# 3_-28pins_sch.net
KiCad netlist of a schematic drawn in Altium Designer
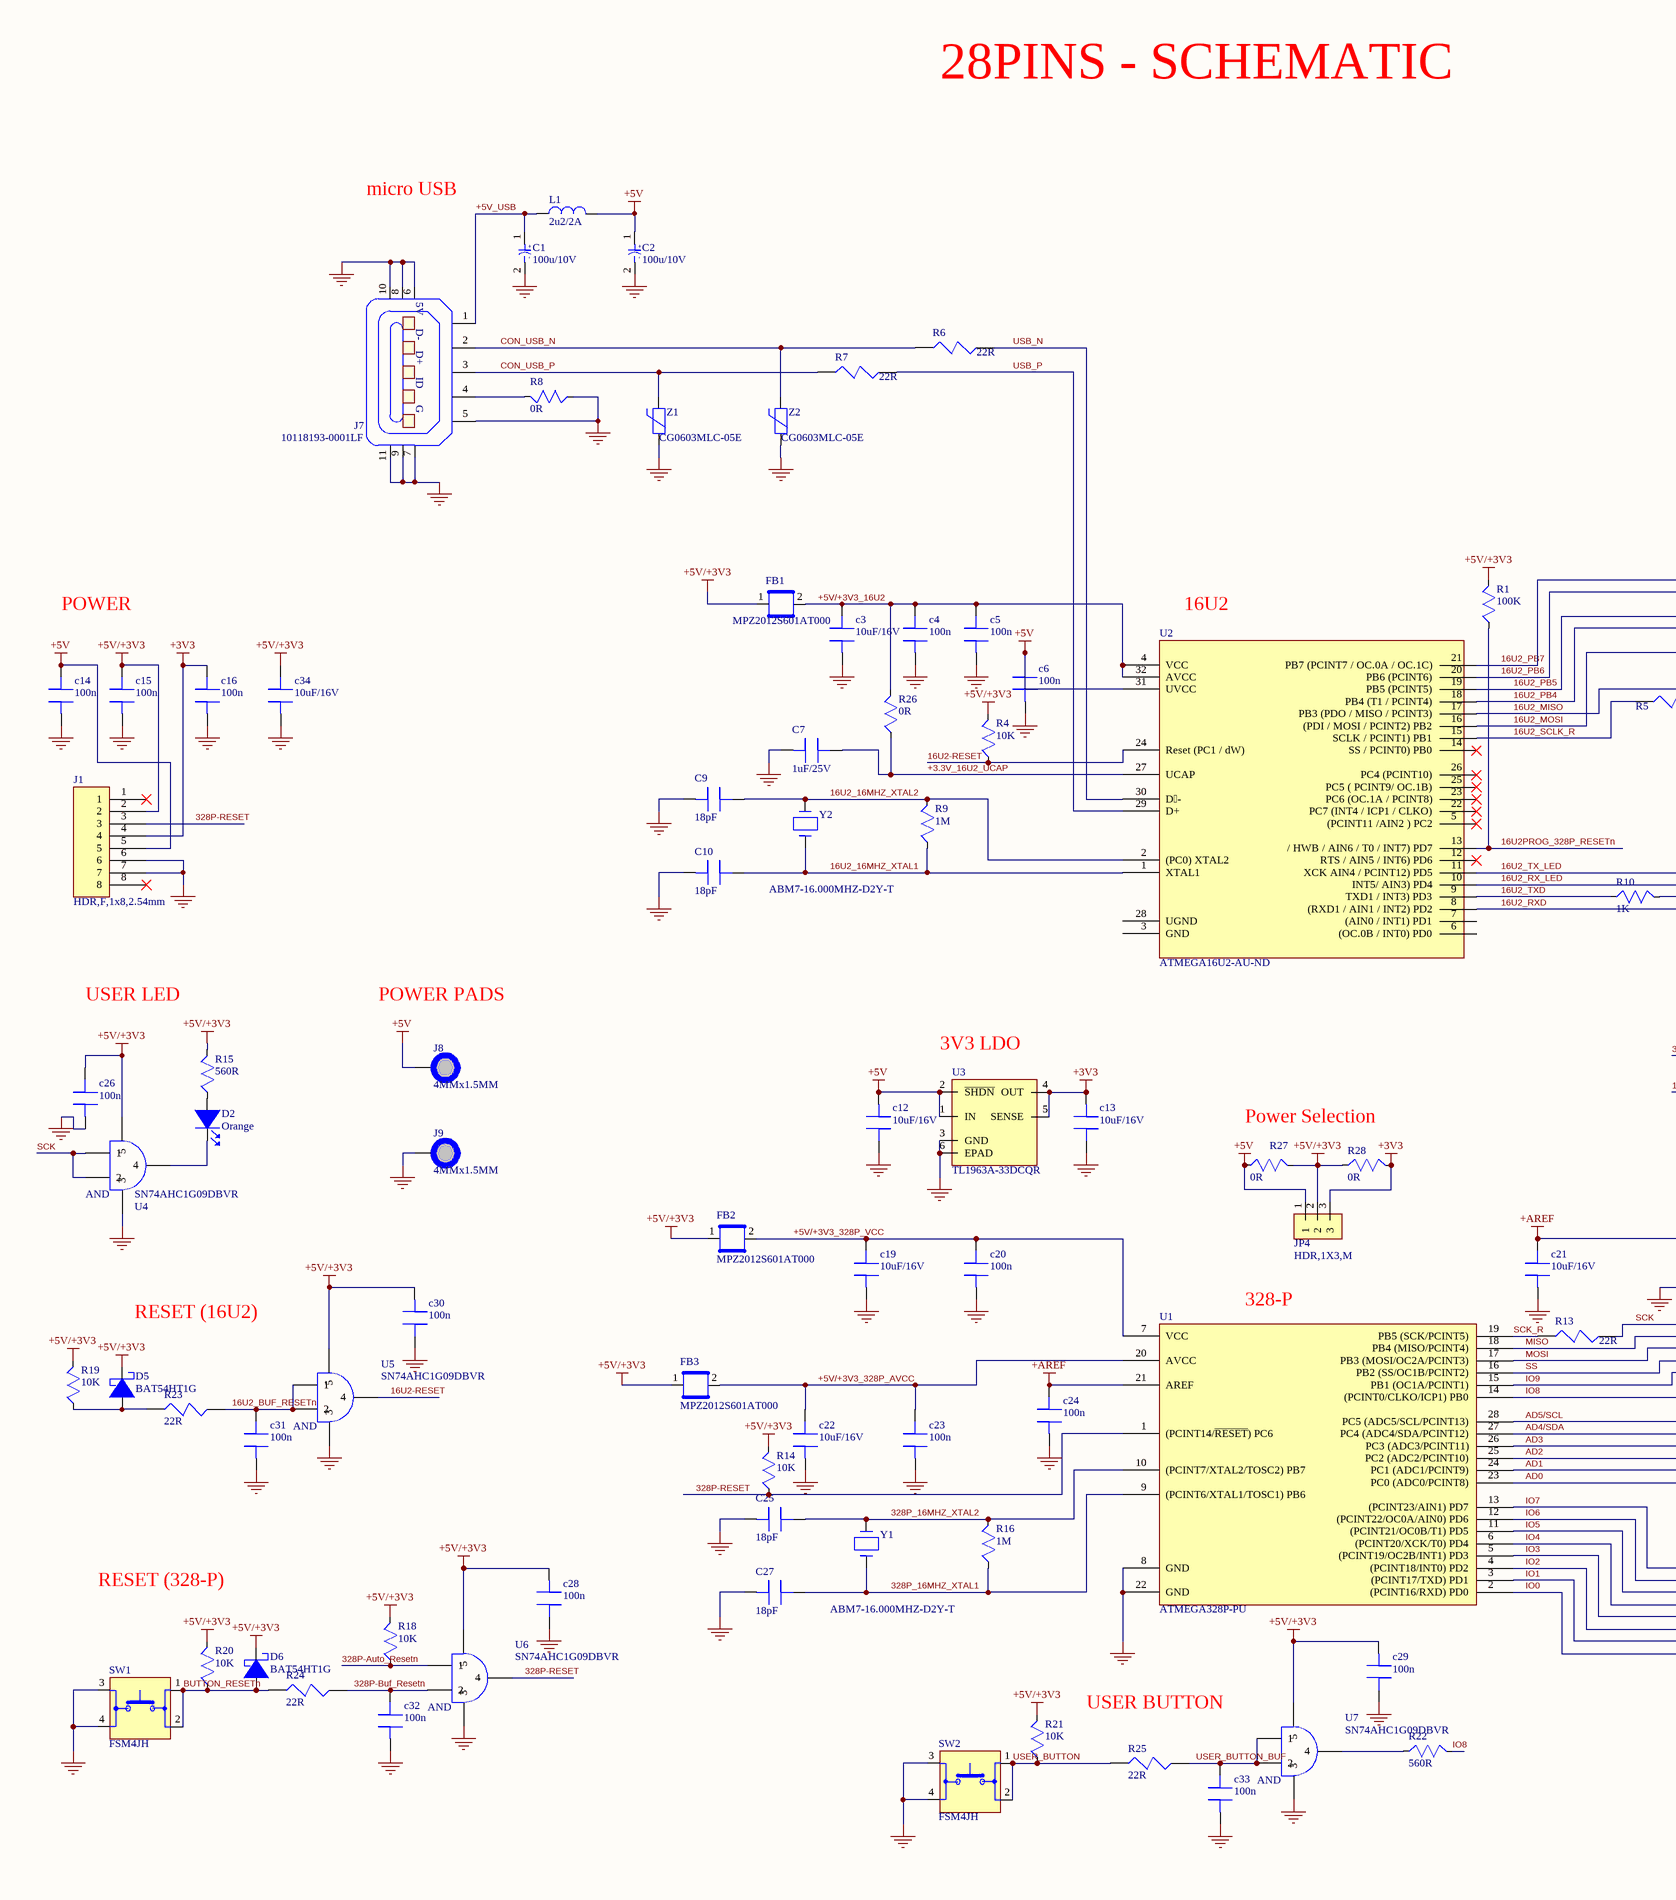
[diagram p0: [3] -28pins_sch.SchDoc, left]
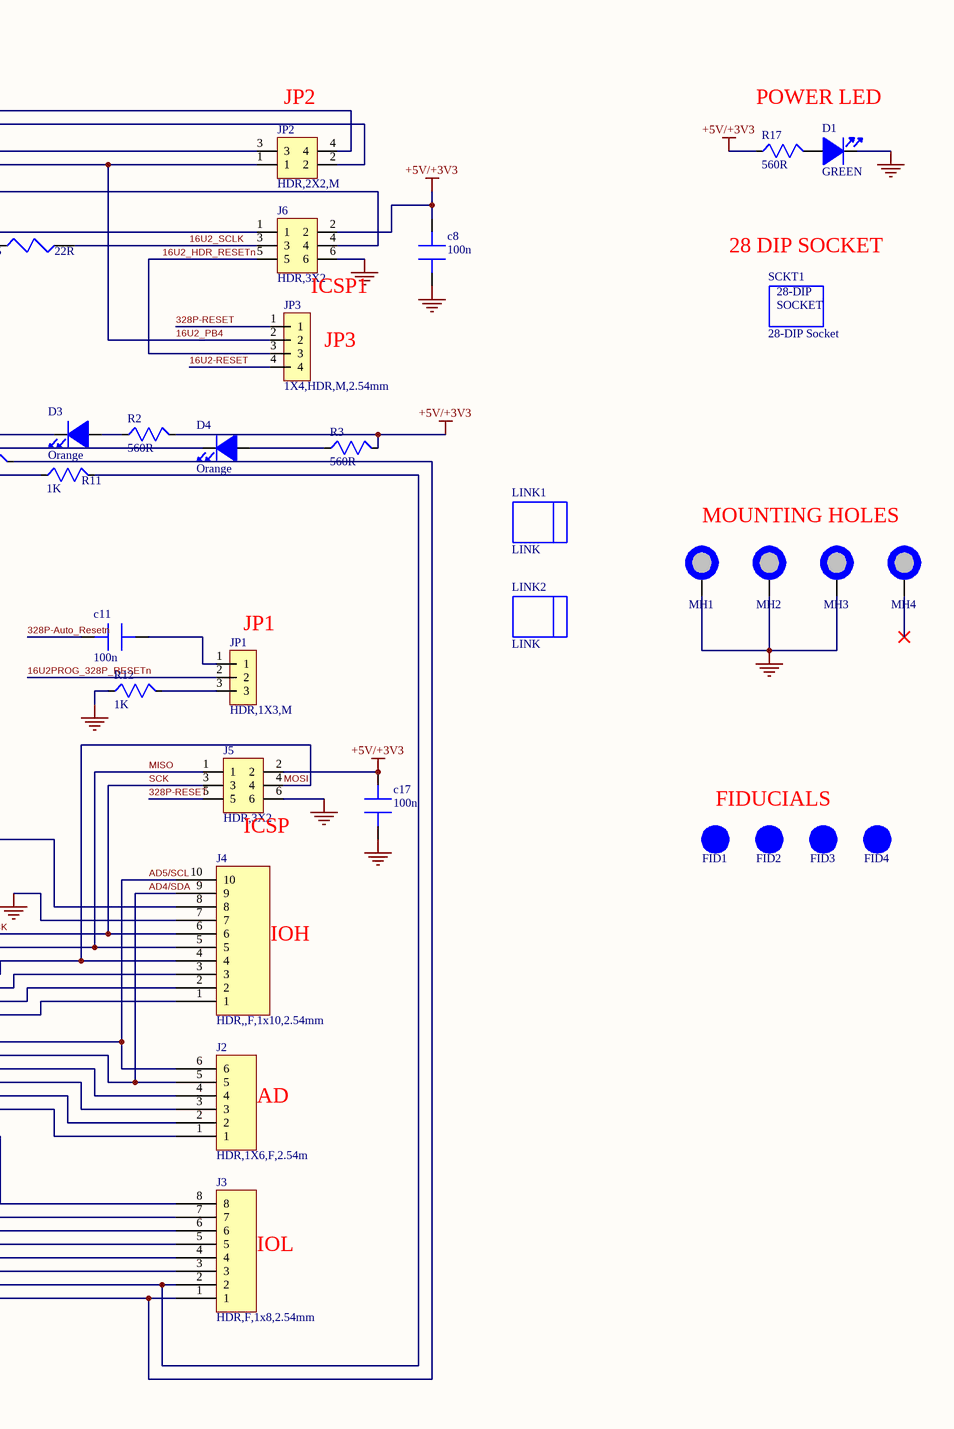
[diagram p1: [3] -28pins_sch.SchDoc, right]

(export (version "E")
  (design (tool "Eeschema 10.0.6"))
  (components
    (comp (ref "C1")
      (value "100u/10V")
      (footprint "C_ALUM")
      (fields
        (field (name "MANUFACTURER") "Panasonic")
        (field (name "MANUFACTURER PART NUMBER") "EEE-1AA101WR")
      )
      (libsource (lib "28pins_Schlib1") (part "EEE-1AA101WR"))
    )
    (comp (ref "C2")
      (value "100u/10V")
      (footprint "C_ALUM")
      (fields
        (field (name "MANUFACTURER") "Panasonic")
        (field (name "MANUFACTURER PART NUMBER") "EEE-1AA101WR")
      )
      (libsource (lib "28pins_Schlib1") (part "EEE-1AA101WR"))
    )
    (comp (ref "c3")
      (value "10uF/16V")
      (footprint "X5R 0805")
      (fields
        (field (name "MANUFACTURER") "TDK")
        (field (name "MANUFACTURER PART NUMBER") "C2012X5R1C106K085AC")
      )
      (libsource (lib "28pins_Schlib1") (part "C2012X5R1C106K085AC"))
    )
    (comp (ref "c4")
      (value "100n")
      (footprint "C0805")
      (fields
        (field (name "MANUFACTURER") "Samsung")
        (field (name "MANUFACTURER PART NUMBER") "CL21B104KBCNNNC")
      )
      (libsource (lib "28pins_Schlib1") (part "CL21B104KBCNNNC"))
    )
    (comp (ref "c5")
      (value "100n")
      (footprint "C0805")
      (fields
        (field (name "MANUFACTURER") "Samsung")
        (field (name "MANUFACTURER PART NUMBER") "CL21B104KBCNNNC")
      )
      (libsource (lib "28pins_Schlib1") (part "CL21B104KBCNNNC"))
    )
    (comp (ref "c6")
      (value "100n")
      (footprint "C0805")
      (fields
        (field (name "MANUFACTURER") "Samsung")
        (field (name "MANUFACTURER PART NUMBER") "CL21B104KBCNNNC")
      )
      (libsource (lib "28pins_Schlib1") (part "CL21B104KBCNNNC"))
    )
    (comp (ref "C7")
      (value "1uF/25V")
      (footprint "C0805")
      (fields
        (field (name "MANUFACTURER") "TDK")
        (field (name "MANUFACTURER PART NUMBER") "C2012X5R1E105K125AA")
      )
      (libsource (lib "28pins_Schlib1") (part "C2012X5R1E105K125AA"))
    )
    (comp (ref "c8")
      (value "100n")
      (footprint "C0805")
      (fields
        (field (name "MANUFACTURER") "Samsung")
        (field (name "MANUFACTURER PART NUMBER") "CL21B104KBCNNNC")
      )
      (libsource (lib "28pins_Schlib1") (part "CL21B104KBCNNNC"))
    )
    (comp (ref "C9")
      (value "18pF")
      (footprint "C0805")
      (fields
        (field (name "MANUFACTURER") "KEMET")
        (field (name "MANUFACTURER PART NUMBER") "C0805C180K5RACTU")
      )
      (libsource (lib "28pins_Schlib1") (part "C0805C180K5RACTU"))
    )
    (comp (ref "C10")
      (value "18pF")
      (footprint "C0805")
      (fields
        (field (name "MANUFACTURER") "KEMET")
        (field (name "MANUFACTURER PART NUMBER") "C0805C180K5RACTU")
      )
      (libsource (lib "28pins_Schlib1") (part "C0805C180K5RACTU"))
    )
    (comp (ref "c11")
      (value "100n")
      (footprint "C0805")
      (fields
        (field (name "MANUFACTURER") "Samsung")
        (field (name "MANUFACTURER PART NUMBER") "CL21B104KBCNNNC")
      )
      (libsource (lib "28pins_Schlib1") (part "CL21B104KBCNNNC"))
    )
    (comp (ref "c12")
      (value "10uF/16V")
      (footprint "X5R 0805")
      (fields
        (field (name "MANUFACTURER") "TDK")
        (field (name "MANUFACTURER PART NUMBER") "C2012X5R1C106K085AC")
      )
      (libsource (lib "28pins_Schlib1") (part "C2012X5R1C106K085AC"))
    )
    (comp (ref "c13")
      (value "10uF/16V")
      (footprint "X5R 0805")
      (fields
        (field (name "MANUFACTURER") "TDK")
        (field (name "MANUFACTURER PART NUMBER") "C2012X5R1C106K085AC")
      )
      (libsource (lib "28pins_Schlib1") (part "C2012X5R1C106K085AC"))
    )
    (comp (ref "c14")
      (value "100n")
      (footprint "C0805")
      (fields
        (field (name "MANUFACTURER") "Samsung")
        (field (name "MANUFACTURER PART NUMBER") "CL21B104KBCNNNC")
      )
      (libsource (lib "28pins_Schlib1") (part "CL21B104KBCNNNC"))
    )
    (comp (ref "c15")
      (value "100n")
      (footprint "C0805")
      (fields
        (field (name "MANUFACTURER") "Samsung")
        (field (name "MANUFACTURER PART NUMBER") "CL21B104KBCNNNC")
      )
      (libsource (lib "28pins_Schlib1") (part "CL21B104KBCNNNC"))
    )
    (comp (ref "c16")
      (value "100n")
      (footprint "C0805")
      (fields
        (field (name "MANUFACTURER") "Samsung")
        (field (name "MANUFACTURER PART NUMBER") "CL21B104KBCNNNC")
      )
      (libsource (lib "28pins_Schlib1") (part "CL21B104KBCNNNC"))
    )
    (comp (ref "c17")
      (value "100n")
      (footprint "C0805")
      (fields
        (field (name "MANUFACTURER") "Samsung")
        (field (name "MANUFACTURER PART NUMBER") "CL21B104KBCNNNC")
      )
      (libsource (lib "28pins_Schlib1") (part "CL21B104KBCNNNC"))
    )
    (comp (ref "c19")
      (value "10uF/16V")
      (footprint "X5R 0805")
      (fields
        (field (name "MANUFACTURER") "TDK")
        (field (name "MANUFACTURER PART NUMBER") "C2012X5R1C106K085AC")
      )
      (libsource (lib "28pins_Schlib1") (part "C2012X5R1C106K085AC"))
    )
    (comp (ref "c20")
      (value "100n")
      (footprint "C0805")
      (fields
        (field (name "MANUFACTURER") "Samsung")
        (field (name "MANUFACTURER PART NUMBER") "CL21B104KBCNNNC")
      )
      (libsource (lib "28pins_Schlib1") (part "CL21B104KBCNNNC"))
    )
    (comp (ref "c21")
      (value "10uF/16V")
      (footprint "X5R 0805")
      (fields
        (field (name "MANUFACTURER") "TDK")
        (field (name "MANUFACTURER PART NUMBER") "C2012X5R1C106K085AC")
      )
      (libsource (lib "28pins_Schlib1") (part "C2012X5R1C106K085AC"))
    )
    (comp (ref "c22")
      (value "10uF/16V")
      (footprint "X5R 0805")
      (fields
        (field (name "MANUFACTURER") "TDK")
        (field (name "MANUFACTURER PART NUMBER") "C2012X5R1C106K085AC")
      )
      (libsource (lib "28pins_Schlib1") (part "C2012X5R1C106K085AC"))
    )
    (comp (ref "c23")
      (value "100n")
      (footprint "C0805")
      (fields
        (field (name "MANUFACTURER") "Samsung")
        (field (name "MANUFACTURER PART NUMBER") "CL21B104KBCNNNC")
      )
      (libsource (lib "28pins_Schlib1") (part "CL21B104KBCNNNC"))
    )
    (comp (ref "c24")
      (value "100n")
      (footprint "C0805")
      (fields
        (field (name "MANUFACTURER") "Samsung")
        (field (name "MANUFACTURER PART NUMBER") "CL21B104KBCNNNC")
      )
      (libsource (lib "28pins_Schlib1") (part "CL21B104KBCNNNC"))
    )
    (comp (ref "C25")
      (value "18pF")
      (footprint "C0805")
      (fields
        (field (name "MANUFACTURER") "KEMET")
        (field (name "MANUFACTURER PART NUMBER") "C0805C180K5RACTU")
      )
      (libsource (lib "28pins_Schlib1") (part "C0805C180K5RACTU"))
    )
    (comp (ref "c26")
      (value "100n")
      (footprint "C0805")
      (fields
        (field (name "MANUFACTURER") "Samsung")
        (field (name "MANUFACTURER PART NUMBER") "CL21B104KBCNNNC")
      )
      (libsource (lib "28pins_Schlib1") (part "CL21B104KBCNNNC"))
    )
    (comp (ref "C27")
      (value "18pF")
      (footprint "C0805")
      (fields
        (field (name "MANUFACTURER") "KEMET")
        (field (name "MANUFACTURER PART NUMBER") "C0805C180K5RACTU")
      )
      (libsource (lib "28pins_Schlib1") (part "C0805C180K5RACTU"))
    )
    (comp (ref "c28")
      (value "100n")
      (footprint "C0805")
      (fields
        (field (name "MANUFACTURER") "Samsung")
        (field (name "MANUFACTURER PART NUMBER") "CL21B104KBCNNNC")
      )
      (libsource (lib "28pins_Schlib1") (part "CL21B104KBCNNNC"))
    )
    (comp (ref "c29")
      (value "100n")
      (footprint "C0805")
      (fields
        (field (name "MANUFACTURER") "Samsung")
        (field (name "MANUFACTURER PART NUMBER") "CL21B104KBCNNNC")
      )
      (libsource (lib "28pins_Schlib1") (part "CL21B104KBCNNNC"))
    )
    (comp (ref "c30")
      (value "100n")
      (footprint "C0805")
      (fields
        (field (name "MANUFACTURER") "Samsung")
        (field (name "MANUFACTURER PART NUMBER") "CL21B104KBCNNNC")
      )
      (libsource (lib "28pins_Schlib1") (part "CL21B104KBCNNNC"))
    )
    (comp (ref "c31")
      (value "100n")
      (footprint "C0805")
      (fields
        (field (name "MANUFACTURER") "Samsung")
        (field (name "MANUFACTURER PART NUMBER") "CL21B104KBCNNNC")
      )
      (libsource (lib "28pins_Schlib1") (part "CL21B104KBCNNNC"))
    )
    (comp (ref "c32")
      (value "100n")
      (footprint "C0805")
      (fields
        (field (name "MANUFACTURER") "Samsung")
        (field (name "MANUFACTURER PART NUMBER") "CL21B104KBCNNNC")
      )
      (libsource (lib "28pins_Schlib1") (part "CL21B104KBCNNNC"))
    )
    (comp (ref "c33")
      (value "100n")
      (footprint "C0805")
      (fields
        (field (name "MANUFACTURER") "Samsung")
        (field (name "MANUFACTURER PART NUMBER") "CL21B104KBCNNNC")
      )
      (libsource (lib "28pins_Schlib1") (part "CL21B104KBCNNNC"))
    )
    (comp (ref "c34")
      (value "10uF/16V")
      (footprint "X5R 0805")
      (fields
        (field (name "MANUFACTURER") "TDK")
        (field (name "MANUFACTURER PART NUMBER") "C2012X5R1C106K085AC")
      )
      (libsource (lib "28pins_Schlib1") (part "C2012X5R1C106K085AC"))
    )
    (comp (ref "D1")
      (value "GREEN")
      (footprint "LED_0603")
      (description "Single Color LED")
      (fields
        (field (name "MANUFACTURER") "SunLED")
        (field (name "MANUFACTURER PART NUMBER") "XZCDGK53W-8VF")
      )
      (libsource (lib "28pins_Schlib1") (part "XZCDGK53W-8VF"))
    )
    (comp (ref "D2")
      (value "Orange")
      (footprint "LED_0603")
      (description "Single Color LED Array, Orange, Transparent Clear, 1.2mm")
      (fields (field (name "MANUFACTURER") "Rohm") (field (name "MANUFACTURER PART NUMBER") "SML-311DTT86"))
      (libsource (lib "28pins_Schlib1") (part "SML-311DTT86"))
    )
    (comp (ref "D3")
      (value "Orange")
      (footprint "LED_0603")
      (description "Single Color LED Array, Orange, Transparent Clear, 1.2mm")
      (fields (field (name "MANUFACTURER") "Rohm") (field (name "MANUFACTURER PART NUMBER") "SML-311DTT86"))
      (libsource (lib "28pins_Schlib1") (part "SML-311DTT86"))
    )
    (comp (ref "D4")
      (value "Orange")
      (footprint "LED_0603")
      (description "Single Color LED Array, Orange, Transparent Clear, 1.2mm")
      (fields (field (name "MANUFACTURER") "Rohm") (field (name "MANUFACTURER PART NUMBER") "SML-311DTT86"))
      (libsource (lib "28pins_Schlib1") (part "SML-311DTT86"))
    )
    (comp (ref "D5")
      (value "BAT54HT1G")
      (footprint "SOD323")
      (description "Rectifier Diode, 1 Phase, 1 Element, 0.2A, 30V V(RRM), Silicon")
      (fields (field (name "MANUFACTURER") "ON Semiconductor / Fairchild"))
      (libsource (lib "28pins_Schlib1") (part "BAT54HT1G"))
    )
    (comp (ref "D6")
      (value "BAT54HT1G")
      (footprint "SOD323")
      (description "Rectifier Diode, 1 Phase, 1 Element, 0.2A, 30V V(RRM), Silicon")
      (fields (field (name "MANUFACTURER") "ON Semiconductor / Fairchild"))
      (libsource (lib "28pins_Schlib1") (part "BAT54HT1G"))
    )
    (comp (ref "FB1")
      (value "MPZ2012S601AT000")
      (footprint "C0805")
      (description "Ferrite Chip, 1 Function(s), 2A")
      (fields (field (name "MANUFACTURER") "TDK"))
      (libsource (lib "28pins_Schlib1") (part "MPZ2012S601AT000"))
    )
    (comp (ref "FB2")
      (value "MPZ2012S601AT000")
      (footprint "C0805")
      (description "Ferrite Chip, 1 Function(s), 2A")
      (fields (field (name "MANUFACTURER") "TDK"))
      (libsource (lib "28pins_Schlib1") (part "MPZ2012S601AT000"))
    )
    (comp (ref "FB3")
      (value "MPZ2012S601AT000")
      (footprint "C0805")
      (description "Ferrite Chip, 1 Function(s), 2A")
      (fields (field (name "MANUFACTURER") "TDK"))
      (libsource (lib "28pins_Schlib1") (part "MPZ2012S601AT000"))
    )
    (comp (ref "FID1")
      (value "1MMC")
      (footprint "FID _40x120D")
      (description "Fiducial 45mm Diameter, 120 mil mask")
      (libsource (lib "28pins_Schlib1") (part "FID_1MMC"))
    )
    (comp (ref "FID2")
      (value "1MMC")
      (footprint "FID _40x120D")
      (description "Fiducial 45mm Diameter, 120 mil mask")
      (libsource (lib "28pins_Schlib1") (part "FID_1MMC"))
    )
    (comp (ref "FID3")
      (value "1MMC")
      (footprint "FID _40x120D")
      (description "Fiducial 45mm Diameter, 120 mil mask")
      (libsource (lib "28pins_Schlib1") (part "FID_1MMC"))
    )
    (comp (ref "FID4")
      (value "1MMC")
      (footprint "FID _40x120D")
      (description "Fiducial 45mm Diameter, 120 mil mask")
      (libsource (lib "28pins_Schlib1") (part "FID_1MMC"))
    )
    (comp (ref "J1")
      (value "HDR,F,1x8,2.54mm")
      (footprint "HDR,F,1X8,2.54mm")
      (fields (field (name "MANUFACTURER") "Harwin") (field (name "MANUFACTURER PART NUMBER") "M20-7820842"))
      (libsource (lib "") (part "M20-7820842_1"))
    )
    (comp (ref "J2")
      (value "HDR,1X6,F,2.54m")
      (footprint "HDR,1X6,F,2.54mm")
      (fields (field (name "MANUFACTURER") "Harwin") (field (name "MANUFACTURER PART NUMBER") "M20-7820646"))
      (libsource (lib "28pins_Schlib1") (part "M20-7820646"))
    )
    (comp (ref "J3")
      (value "HDR,F,1x8,2.54mm")
      (footprint "HDR,F,1X8,2.54mm")
      (fields (field (name "MANUFACTURER") "Harwin") (field (name "MANUFACTURER PART NUMBER") "M20-7820842"))
      (libsource (lib "28pins_Schlib1") (part "M20-7820842"))
    )
    (comp (ref "J4")
      (value "HDR,,F,1x10,2.54mm")
      (footprint "HDR,F,1x10,2.54mm")
      (fields (field (name "MANUFACTURER") "Harwin") (field (name "MANUFACTURER PART NUMBER") "M20-7821046"))
      (libsource (lib "28pins_Schlib1") (part "M20-7821046"))
    )
    (comp (ref "J5")
      (value "HDR,3X2")
      (footprint "HDR,2X3,2.54mm")
      (description "Conn Unshrouded Header HDR 6 POS 2.54mm Solder ST Top Entry Thru-Hole BergStik® Bulk")
      (fields
        (field (name "MANUFACTURER") "Amphenol ICC / FCI")
        (field (name "MANUFACTURER PART NUMBER") "67997-106HLF")
      )
      (libsource (lib "28pins_Schlib1") (part "67997-106HLF"))
    )
    (comp (ref "J6")
      (value "HDR,3X2")
      (footprint "HDR,2X3,2.54mm")
      (description "Conn Unshrouded Header HDR 6 POS 2.54mm Solder ST Top Entry Thru-Hole BergStik® Bulk")
      (fields
        (field (name "MANUFACTURER") "Amphenol ICC / FCI")
        (field (name "MANUFACTURER PART NUMBER") "67997-106HLF")
      )
      (libsource (lib "28pins_Schlib1") (part "67997-106HLF"))
    )
    (comp (ref "J7")
      (value "10118193-0001LF")
      (footprint "10118193")
      (description "FCI Right Angle Surface Mount Mount Female USB Connector; 100 V ac; 1.8A")
      (fields (field (name "MANUFACTURER") "Amphenol ICC / FCI"))
      (libsource (lib "28pins_Schlib1") (part "10118193-0001LF"))
    )
    (comp (ref "J8")
      (value "4MMx1.5MM")
      (footprint "pad_with_holes_4MMx1.5MM")
      (description "pad with holes, 4MMx1.5MM")
      (libsource (lib "28pins_Schlib1") (part "pad_with_hole_4MMx1.5MM"))
    )
    (comp (ref "J9")
      (value "4MMx1.5MM")
      (footprint "pad_with_holes_4MMx1.5MM")
      (description "pad with holes, 4MMx1.5MM")
      (libsource (lib "28pins_Schlib1") (part "pad_with_hole_4MMx1.5MM"))
    )
    (comp (ref "JP1")
      (value "HDR,1X3,M")
      (footprint "HDR,1X3,M,2.54mm")
      (description "Conn Unshrouded Header HDR 3 POS 2.54mm Solder ST Top Entry Thru-Hole BergStik® Automotive Bulk")
      (fields
        (field (name "MANUFACTURER") "Amphenol ICC / FCI")
        (field (name "MANUFACTURER PART NUMBER") "68000-103HLF")
      )
      (libsource (lib "28pins_Schlib1") (part "68000-103HLF"))
    )
    (comp (ref "JP2")
      (value "HDR,2X2,M")
      (footprint "HDR,2X2,2.54mm")
      (description "Conn Unshrouded Header HDR 4 POS 2.54mm Solder ST Top Entry Thru-Hole BergStik® Bulk")
      (fields
        (field (name "MANUFACTURER") "Amphenol ICC / FCI")
        (field (name "MANUFACTURER PART NUMBER") "67996-104HLF")
      )
      (libsource (lib "28pins_Schlib1") (part "67996-104HLF"))
    )
    (comp (ref "JP3")
      (value "1X4,HDR,M,2.54mm")
      (footprint "HDR,1X4,M,2.54mm")
      (description "Conn Unshrouded Header HDR 4 POS 2.54mm Solder ST Thru-Hole Bag")
      (fields
        (field (name "MANUFACTURER") "Amphenol ICC / FCI")
        (field (name "MANUFACTURER PART NUMBER") "68001-204HLF")
      )
      (libsource (lib "28pins_Schlib1") (part "68001-204HLF"))
    )
    (comp (ref "JP4")
      (value "HDR,1X3,M")
      (footprint "HDR,1X3,M,2.54mm")
      (description "Conn Unshrouded Header HDR 3 POS 2.54mm Solder ST Top Entry Thru-Hole BergStik® Automotive Bulk")
      (fields
        (field (name "MANUFACTURER") "Amphenol ICC / FCI")
        (field (name "MANUFACTURER PART NUMBER") "68000-103HLF")
      )
      (libsource (lib "") (part "68000-103HLF_1"))
    )
    (comp (ref "L1")
      (value "2u2/2A")
      (footprint "INDUCTOR")
      (description "General Purpose Inductor, 2.2uH, 20%, 1 Element, Metal Composite-Core, SMD")
      (fields
        (field (name "MANUFACTURER") "Samsung")
        (field (name "MANUFACTURER PART NUMBER") "CIGT252008LM2R2MNE")
      )
      (libsource (lib "28pins_Schlib1") (part "CIGT252008LM2R2MNE"))
    )
    (comp (ref "LINK1")
      (value "LINK")
      (description "Shunts/Jumper Connector")
      (fields
        (field (name "MANUFACTURER") "Sullins")
        (field (name "MANUFACTURER PART NUMBER") "QPC02SXGN-RC")
      )
      (libsource (lib "28pins_Schlib1") (part "QPC02SXGN-RC"))
    )
    (comp (ref "LINK2")
      (value "LINK")
      (description "Shunts/Jumper Connector")
      (fields
        (field (name "MANUFACTURER") "Sullins")
        (field (name "MANUFACTURER PART NUMBER") "QPC02SXGN-RC")
      )
      (libsource (lib "28pins_Schlib1") (part "QPC02SXGN-RC"))
    )
    (comp (ref "MH1")
      (value "MH_7.4MM,drill")
      (footprint "MH_7.4MM")
      (libsource (lib "28pins_Schlib1") (part "MH_7.4MM"))
    )
    (comp (ref "MH2")
      (value "MH_7.4MM,drill")
      (footprint "MH_7.4MM")
      (libsource (lib "28pins_Schlib1") (part "MH_7.4MM"))
    )
    (comp (ref "MH3")
      (value "MH_7.4MM,drill")
      (footprint "MH_7.4MM")
      (libsource (lib "28pins_Schlib1") (part "MH_7.4MM"))
    )
    (comp (ref "MH4")
      (value "MH_7.4_noncoppper_nonplated")
      (footprint "MH7.44_nonplated_nonecopper")
      (libsource (lib "28pins_Schlib1") (part "MH_7.44_noncopper_nonplated"))
    )
    (comp (ref "R1")
      (value "100K")
      (footprint "R0805")
      (fields
        (field (name "MANUFACTURER") "Yageo")
        (field (name "MANUFACTURER PART NUMBER") "AC0805FR-13100KL")
        (field (name "TOLERANCE") "1%")
      )
      (libsource (lib "28pins_Schlib1") (part "AC0805FR-13100KL"))
    )
    (comp (ref "R2")
      (value "560R")
      (footprint "R0805")
      (fields
        (field (name "MANUFACTURER") "Yageo")
        (field (name "MANUFACTURER PART NUMBER") "RC0805FR-10560RL")
        (field (name "TOLERANCE") "1%")
      )
      (libsource (lib "28pins_Schlib1") (part "RC0805FR-10560RL"))
    )
    (comp (ref "R3")
      (value "560R")
      (footprint "R0805")
      (fields
        (field (name "MANUFACTURER") "Yageo")
        (field (name "MANUFACTURER PART NUMBER") "RC0805FR-10560RL")
        (field (name "TOLERANCE") "1%")
      )
      (libsource (lib "28pins_Schlib1") (part "RC0805FR-10560RL"))
    )
    (comp (ref "R4")
      (value "10K")
      (footprint "R0805")
      (fields
        (field (name "MANUFACTURER") "Yageo")
        (field (name "MANUFACTURER PART NUMBER") "RC0805FR-0710KL")
        (field (name "TOLERANCE") "1%")
      )
      (libsource (lib "28pins_Schlib1") (part "RC0805FR-0710KL"))
    )
    (comp (ref "R5")
      (value "22R")
      (footprint "R0805")
      (fields
        (field (name "MANUFACTURER") "Yageo")
        (field (name "MANUFACTURER PART NUMBER") "AC0805FR-0722RL")
        (field (name "TOLERANCE") "1%")
      )
      (libsource (lib "28pins_Schlib1") (part "AC0805FR-0722RL"))
    )
    (comp (ref "R6")
      (value "22R")
      (footprint "R0805")
      (fields
        (field (name "MANUFACTURER") "Yageo")
        (field (name "MANUFACTURER PART NUMBER") "AC0805FR-0722RL")
        (field (name "TOLERANCE") "1%")
      )
      (libsource (lib "28pins_Schlib1") (part "AC0805FR-0722RL"))
    )
    (comp (ref "R7")
      (value "22R")
      (footprint "R0805")
      (fields
        (field (name "MANUFACTURER") "Yageo")
        (field (name "MANUFACTURER PART NUMBER") "AC0805FR-0722RL")
        (field (name "TOLERANCE") "1%")
      )
      (libsource (lib "28pins_Schlib1") (part "AC0805FR-0722RL"))
    )
    (comp (ref "R8")
      (value "0R")
      (footprint "R0805")
      (description "Metal Glaze/thick Film, 0.125W, 0ohm, Surface Mount, 0805")
      (fields
        (field (name "MANUFACTURER") "Yageo")
        (field (name "MANUFACTURER PART NUMBER") "RC0805JR-070RL")
      )
      (libsource (lib "28pins_Schlib1") (part "RC0805JR-070RL"))
    )
    (comp (ref "R9")
      (value "1M")
      (footprint "R0805")
      (fields
        (field (name "MANUFACTURER") "Yageo")
        (field (name "MANUFACTURER PART NUMBER") "RC0805FR-071ML")
        (field (name "TOLERANCE") "1%")
      )
      (libsource (lib "28pins_Schlib1") (part "RC0805FR-071ML"))
    )
    (comp (ref "R10")
      (value "1K")
      (footprint "R0805")
      (fields
        (field (name "MANUFACTURER") "Yageo")
        (field (name "MANUFACTURER PART NUMBER") "RC0805FR-071KL")
        (field (name "TOLERANCE") "1%")
      )
      (libsource (lib "28pins_Schlib1") (part "RC0805FR-071KL"))
    )
    (comp (ref "R11")
      (value "1K")
      (footprint "R0805")
      (fields
        (field (name "MANUFACTURER") "Yageo")
        (field (name "MANUFACTURER PART NUMBER") "RC0805FR-071KL")
        (field (name "TOLERANCE") "1%")
      )
      (libsource (lib "28pins_Schlib1") (part "RC0805FR-071KL"))
    )
    (comp (ref "R12")
      (value "1K")
      (footprint "R0805")
      (fields
        (field (name "MANUFACTURER") "Yageo")
        (field (name "MANUFACTURER PART NUMBER") "RC0805FR-071KL")
        (field (name "TOLERANCE") "1%")
      )
      (libsource (lib "28pins_Schlib1") (part "RC0805FR-071KL"))
    )
    (comp (ref "R13")
      (value "22R")
      (footprint "R0805")
      (fields
        (field (name "MANUFACTURER") "Yageo")
        (field (name "MANUFACTURER PART NUMBER") "AC0805FR-0722RL")
        (field (name "TOLERANCE") "1%")
      )
      (libsource (lib "28pins_Schlib1") (part "AC0805FR-0722RL"))
    )
    (comp (ref "R14")
      (value "10K")
      (footprint "R0805")
      (fields
        (field (name "MANUFACTURER") "Yageo")
        (field (name "MANUFACTURER PART NUMBER") "RC0805FR-0710KL")
        (field (name "TOLERANCE") "1%")
      )
      (libsource (lib "28pins_Schlib1") (part "RC0805FR-0710KL"))
    )
    (comp (ref "R15")
      (value "560R")
      (footprint "R0805")
      (fields
        (field (name "MANUFACTURER") "Yageo")
        (field (name "MANUFACTURER PART NUMBER") "RC0805FR-10560RL")
        (field (name "TOLERANCE") "1%")
      )
      (libsource (lib "28pins_Schlib1") (part "RC0805FR-10560RL"))
    )
    (comp (ref "R16")
      (value "1M")
      (footprint "R0805")
      (fields
        (field (name "MANUFACTURER") "Yageo")
        (field (name "MANUFACTURER PART NUMBER") "RC0805FR-071ML")
        (field (name "TOLERANCE") "1%")
      )
      (libsource (lib "28pins_Schlib1") (part "RC0805FR-071ML"))
    )
    (comp (ref "R17")
      (value "560R")
      (footprint "R0805")
      (fields
        (field (name "MANUFACTURER") "Yageo")
        (field (name "MANUFACTURER PART NUMBER") "RC0805FR-10560RL")
        (field (name "TOLERANCE") "1%")
      )
      (libsource (lib "28pins_Schlib1") (part "RC0805FR-10560RL"))
    )
    (comp (ref "R18")
      (value "10K")
      (footprint "R0805")
      (fields
        (field (name "MANUFACTURER") "Yageo")
        (field (name "MANUFACTURER PART NUMBER") "RC0805FR-0710KL")
        (field (name "TOLERANCE") "1%")
      )
      (libsource (lib "28pins_Schlib1") (part "RC0805FR-0710KL"))
    )
    (comp (ref "R19")
      (value "10K")
      (footprint "R0805")
      (fields
        (field (name "MANUFACTURER") "Yageo")
        (field (name "MANUFACTURER PART NUMBER") "RC0805FR-0710KL")
        (field (name "TOLERANCE") "1%")
      )
      (libsource (lib "28pins_Schlib1") (part "RC0805FR-0710KL"))
    )
    (comp (ref "R20")
      (value "10K")
      (footprint "R0805")
      (fields
        (field (name "MANUFACTURER") "Yageo")
        (field (name "MANUFACTURER PART NUMBER") "RC0805FR-0710KL")
        (field (name "TOLERANCE") "1%")
      )
      (libsource (lib "28pins_Schlib1") (part "RC0805FR-0710KL"))
    )
    (comp (ref "R21")
      (value "10K")
      (footprint "R0805")
      (fields
        (field (name "MANUFACTURER") "Yageo")
        (field (name "MANUFACTURER PART NUMBER") "RC0805FR-0710KL")
        (field (name "TOLERANCE") "1%")
      )
      (libsource (lib "28pins_Schlib1") (part "RC0805FR-0710KL"))
    )
    (comp (ref "R22")
      (value "560R")
      (footprint "R0805")
      (fields
        (field (name "MANUFACTURER") "Yageo")
        (field (name "MANUFACTURER PART NUMBER") "RC0805FR-10560RL")
        (field (name "TOLERANCE") "1%")
      )
      (libsource (lib "28pins_Schlib1") (part "RC0805FR-10560RL"))
    )
    (comp (ref "R23")
      (value "22R")
      (footprint "R0805")
      (fields
        (field (name "MANUFACTURER") "Yageo")
        (field (name "MANUFACTURER PART NUMBER") "AC0805FR-0722RL")
        (field (name "TOLERANCE") "1%")
      )
      (libsource (lib "28pins_Schlib1") (part "AC0805FR-0722RL"))
    )
    (comp (ref "R24")
      (value "22R")
      (footprint "R0805")
      (fields
        (field (name "MANUFACTURER") "Yageo")
        (field (name "MANUFACTURER PART NUMBER") "AC0805FR-0722RL")
        (field (name "TOLERANCE") "1%")
      )
      (libsource (lib "28pins_Schlib1") (part "AC0805FR-0722RL"))
    )
    (comp (ref "R25")
      (value "22R")
      (footprint "R0805")
      (fields
        (field (name "MANUFACTURER") "Yageo")
        (field (name "MANUFACTURER PART NUMBER") "AC0805FR-0722RL")
        (field (name "TOLERANCE") "1%")
      )
      (libsource (lib "28pins_Schlib1") (part "AC0805FR-0722RL"))
    )
    (comp (ref "R26")
      (value "0R")
      (footprint "R0805")
      (description "Metal Glaze/thick Film, 0.125W, 0ohm, Surface Mount, 0805")
      (fields
        (field (name "MANUFACTURER") "Yageo")
        (field (name "MANUFACTURER PART NUMBER") "RC0805JR-070RL")
      )
      (libsource (lib "28pins_Schlib1") (part "RC0805JR-070RL"))
    )
    (comp (ref "R27")
      (value "0R")
      (footprint "R0805")
      (description "Metal Glaze/thick Film, 0.125W, 0ohm, Surface Mount, 0805")
      (fields
        (field (name "MANUFACTURER") "Yageo")
        (field (name "MANUFACTURER PART NUMBER") "RC0805JR-070RL")
      )
      (libsource (lib "28pins_Schlib1") (part "RC0805JR-070RL"))
    )
    (comp (ref "R28")
      (value "0R")
      (footprint "R0805")
      (description "Metal Glaze/thick Film, 0.125W, 0ohm, Surface Mount, 0805")
      (fields
        (field (name "MANUFACTURER") "Yageo")
        (field (name "MANUFACTURER PART NUMBER") "RC0805JR-070RL")
      )
      (libsource (lib "28pins_Schlib1") (part "RC0805JR-070RL"))
    )
    (comp (ref "SCKT1")
      (value "28-DIP Socket")
      (footprint "28_DIP_SCKT")
      (description "IC Socket, DIP28, 28 Contact(s)")
      (fields (field (name "MANUFACTURER") "3M") (field (name "MANUFACTURER PART NUMBER") "4828-3004-CP"))
      (libsource (lib "28pins_Schlib1") (part "4828-3004-CP"))
    )
    (comp (ref "SW1")
      (value "FSM4JH")
      (footprint "SW")
      (description "Keypad Switch, 1 Switches, Momentary-tactile, 0.05A, 1.57N, Solder Terminal, Through Hole-straight")
      (fields (field (name "MANUFACTURER") "TE Connectivity"))
      (libsource (lib "28pins_Schlib1") (part "FSM4JH"))
    )
    (comp (ref "SW2")
      (value "FSM4JH")
      (footprint "SW")
      (description "Keypad Switch, 1 Switches, Momentary-tactile, 0.05A, 1.57N, Solder Terminal, Through Hole-straight")
      (fields (field (name "MANUFACTURER") "TE Connectivity"))
      (libsource (lib "28pins_Schlib1") (part "FSM4JH"))
    )
    (comp (ref "U1")
      (value "ATMEGA328P-PU")
      (footprint "28_DIP_7.62mm")
      (description "RISC Microcontroller, 8-Bit, FLASH, AVR RISC CPU, 20MHz, CMOS, PDIP28")
      (fields (field (name "MANUFACTURER") "Microchip"))
      (libsource (lib "28pins_Schlib1") (part "ATMEGA328P-PU"))
    )
    (comp (ref "U2")
      (value "ATMEGA16U2-AU-ND")
      (footprint "TQFP32")
      (description "RISC Microcontroller, 8-Bit, FLASH, AVR RISC CPU, 16MHz, CMOS, PQFP32")
      (fields
        (field (name "MANUFACTURER") "Microchip")
        (field (name "MANUFACTURER PART NUMBER") "ATMEGA16U2-AU")
      )
      (libsource (lib "28pins_Schlib1") (part "ATMEGA16U2-AU"))
    )
    (comp (ref "U3")
      (value "TL1963A-33DCQR")
      (footprint "DCQ(R-PDSO-G6)")
      (description "Fixed Positive LDO Regulator, 3.3V, 0.55V Dropout, BIPolar, PDSO6")
      (fields (field (name "MANUFACTURER") "Texas Instruments"))
      (libsource (lib "28pins_Schlib1") (part "TL1963A-33DCQR"))
    )
    (comp (ref "U4")
      (value "SN74AHC1G09DBVR")
      (footprint "DBV_SOT")
      (description "AND Gate, AHC/VHC/H/U/V Series, 1-Func, 2-Input, CMOS, PDSO5")
      (fields (field (name "MANUFACTURER") "Texas Instruments"))
      (libsource (lib "28pins_Schlib1") (part "SN74AHC1G09DBVR"))
    )
    (comp (ref "U5")
      (value "SN74AHC1G09DBVR")
      (footprint "DBV_SOT")
      (description "AND Gate, AHC/VHC/H/U/V Series, 1-Func, 2-Input, CMOS, PDSO5")
      (fields (field (name "MANUFACTURER") "Texas Instruments"))
      (libsource (lib "28pins_Schlib1") (part "SN74AHC1G09DBVR"))
    )
    (comp (ref "U6")
      (value "SN74AHC1G09DBVR")
      (footprint "DBV_SOT")
      (description "AND Gate, AHC/VHC/H/U/V Series, 1-Func, 2-Input, CMOS, PDSO5")
      (fields (field (name "MANUFACTURER") "Texas Instruments"))
      (libsource (lib "28pins_Schlib1") (part "SN74AHC1G09DBVR"))
    )
    (comp (ref "U7")
      (value "SN74AHC1G09DBVR")
      (footprint "DBV_SOT")
      (description "AND Gate, AHC/VHC/H/U/V Series, 1-Func, 2-Input, CMOS, PDSO5")
      (fields (field (name "MANUFACTURER") "Texas Instruments"))
      (libsource (lib "28pins_Schlib1") (part "SN74AHC1G09DBVR"))
    )
    (comp (ref "Y1")
      (value "ABM7-16.000MHZ-D2Y-T")
      (footprint "ABM7-16MHz,BIG")
      (description "Crystal 16MHz ±20ppm (Tol) ±30ppm (Stability) 18pF FUND 50Ohm 2-Pin Mini-CSMD T/R")
      (fields (field (name "MANUFACTURER") "Abracon"))
      (libsource (lib "28pins_Schlib1") (part "ABM7-16.000MHZ-D2Y-T"))
    )
    (comp (ref "Y2")
      (value "ABM7-16.000MHZ-D2Y-T")
      (footprint "ABM7-16MHz,BIG")
      (description "Crystal 16MHz ±20ppm (Tol) ±30ppm (Stability) 18pF FUND 50Ohm 2-Pin Mini-CSMD T/R")
      (fields (field (name "MANUFACTURER") "Abracon"))
      (libsource (lib "28pins_Schlib1") (part "ABM7-16.000MHZ-D2Y-T"))
    )
    (comp (ref "Z1")
      (value "CG0603MLC-05E")
      (footprint "R0603")
      (description "Varistor, 5V, Surface Mount")
      (fields (field (name "MANUFACTURER") "Bourns"))
      (libsource (lib "28pins_Schlib1") (part "CG0603MLC-05E"))
    )
    (comp (ref "Z2")
      (value "CG0603MLC-05E")
      (footprint "R0603")
      (description "Varistor, 5V, Surface Mount")
      (fields (field (name "MANUFACTURER") "Bourns"))
      (libsource (lib "28pins_Schlib1") (part "CG0603MLC-05E"))
    )
  )
  (nets
    (net (code "1") (name "+3V3") (class "Default")
      (node (ref "J1") (pin "4") (pinfunction "4_4") (pintype "passive"))
      (node (ref "JP4") (pin "3") (pinfunction "3_3") (pintype "passive"))
      (node (ref "R28") (pin "2") (pinfunction "2_2") (pintype "passive"))
      (node (ref "U3") (pin "4") (pinfunction "OUT_4") (pintype "passive"))
      (node (ref "U3") (pin "5") (pinfunction "SENSE_5") (pintype "passive"))
      (node (ref "c13") (pin "1") (pinfunction "1_1") (pintype "passive"))
      (node (ref "c16") (pin "2") (pinfunction "2_2") (pintype "passive"))
    )
    (net (code "2") (name "+5V") (class "Default")
      (node (ref "C2") (pin "1") (pinfunction "1_1") (pintype "passive"))
      (node (ref "J1") (pin "5") (pinfunction "5_5") (pintype "passive"))
      (node (ref "J8") (pin "1") (pinfunction "1_1") (pintype "open_collector"))
      (node (ref "JP4") (pin "1") (pinfunction "1_1") (pintype "passive"))
      (node (ref "L1") (pin "2") (pinfunction "2_2") (pintype "passive"))
      (node (ref "R27") (pin "1") (pinfunction "1_1") (pintype "passive"))
      (node (ref "U2") (pin "31") (pinfunction "UVCC_31") (pintype "passive"))
      (node (ref "U3") (pin "1") (pinfunction "IN_1") (pintype "passive"))
      (node (ref "U3") (pin "2") (pinfunction "~{SHDN}_2") (pintype "passive"))
      (node (ref "c12") (pin "1") (pinfunction "1_1") (pintype "passive"))
      (node (ref "c14") (pin "2") (pinfunction "2_2") (pintype "passive"))
      (node (ref "c6") (pin "2") (pinfunction "2_2") (pintype "passive"))
    )
    (net (code "3") (name "+5V{slash}+3V3") (class "Default")
      (node (ref "D5") (pin "1") (pinfunction "Cathode_1") (pintype "passive"))
      (node (ref "D6") (pin "1") (pinfunction "Cathode_1") (pintype "passive"))
      (node (ref "FB1") (pin "1") (pinfunction "1_1") (pintype "passive"))
      (node (ref "FB2") (pin "1") (pinfunction "1_1") (pintype "passive"))
      (node (ref "FB3") (pin "1") (pinfunction "1_1") (pintype "passive"))
      (node (ref "J1") (pin "2") (pinfunction "2_2") (pintype "passive"))
      (node (ref "J5") (pin "2") (pinfunction "2_2") (pintype "passive"))
      (node (ref "J6") (pin "2") (pinfunction "2_2") (pintype "passive"))
      (node (ref "JP4") (pin "2") (pinfunction "2_2") (pintype "passive"))
      (node (ref "R1") (pin "2") (pinfunction "2_2") (pintype "passive"))
      (node (ref "R14") (pin "2") (pinfunction "2_2") (pintype "passive"))
      (node (ref "R15") (pin "2") (pinfunction "2_2") (pintype "passive"))
      (node (ref "R17") (pin "1") (pinfunction "1_1") (pintype "passive"))
      (node (ref "R18") (pin "2") (pinfunction "2_2") (pintype "passive"))
      (node (ref "R19") (pin "2") (pinfunction "2_2") (pintype "passive"))
      (node (ref "R2") (pin "2") (pinfunction "2_2") (pintype "passive"))
      (node (ref "R20") (pin "2") (pinfunction "2_2") (pintype "passive"))
      (node (ref "R21") (pin "2") (pinfunction "2_2") (pintype "passive"))
      (node (ref "R27") (pin "2") (pinfunction "2_2") (pintype "passive"))
      (node (ref "R28") (pin "1") (pinfunction "1_1") (pintype "passive"))
      (node (ref "R3") (pin "2") (pinfunction "2_2") (pintype "passive"))
      (node (ref "R4") (pin "2") (pinfunction "2_2") (pintype "passive"))
      (node (ref "U4") (pin "5") (pinfunction "5_5") (pintype "passive"))
      (node (ref "U5") (pin "5") (pinfunction "5_5") (pintype "passive"))
      (node (ref "U6") (pin "5") (pinfunction "5_5") (pintype "passive"))
      (node (ref "U7") (pin "5") (pinfunction "5_5") (pintype "passive"))
      (node (ref "c15") (pin "2") (pinfunction "2_2") (pintype "passive"))
      (node (ref "c17") (pin "2") (pinfunction "2_2") (pintype "passive"))
      (node (ref "c26") (pin "2") (pinfunction "2_2") (pintype "passive"))
      (node (ref "c28") (pin "1") (pinfunction "1_1") (pintype "passive"))
      (node (ref "c29") (pin "1") (pinfunction "1_1") (pintype "passive"))
      (node (ref "c30") (pin "1") (pinfunction "1_1") (pintype "passive"))
      (node (ref "c34") (pin "2") (pinfunction "2_2") (pintype "passive"))
      (node (ref "c8") (pin "2") (pinfunction "2_2") (pintype "passive"))
    )
    (net (code "4") (name "+AREF") (class "Default")
      (node (ref "J4") (pin "8") (pinfunction "8_8") (pintype "passive"))
      (node (ref "U1") (pin "21") (pinfunction "AREF_21") (pintype "passive"))
      (node (ref "c21") (pin "2") (pinfunction "2_2") (pintype "passive"))
      (node (ref "c24") (pin "2") (pinfunction "2_2") (pintype "passive"))
    )
    (net (code "5") (name "/+3.3V_16U2_UCAP") (class "Default")
      (node (ref "C7") (pin "2") (pinfunction "2_2") (pintype "passive"))
      (node (ref "R26") (pin "1") (pinfunction "1_1") (pintype "passive"))
      (node (ref "U2") (pin "27") (pinfunction "UCAP_27") (pintype "passive"))
    )
    (net (code "6") (name "/+5V_USB") (class "Default")
      (node (ref "C1") (pin "1") (pinfunction "1_1") (pintype "passive"))
      (node (ref "J7") (pin "1") (pinfunction "1_1") (pintype "passive"))
      (node (ref "L1") (pin "1") (pinfunction "1_1") (pintype "passive"))
    )
    (net (code "7") (name "/+5V{slash}+3V3_16U2") (class "Default")
      (node (ref "FB1") (pin "2") (pinfunction "2_2") (pintype "passive"))
      (node (ref "R26") (pin "2") (pinfunction "2_2") (pintype "passive"))
      (node (ref "U2") (pin "32") (pinfunction "AVCC_32") (pintype "passive"))
      (node (ref "U2") (pin "4") (pinfunction "VCC_4") (pintype "passive"))
      (node (ref "c3") (pin "2") (pinfunction "2_2") (pintype "passive"))
      (node (ref "c4") (pin "2") (pinfunction "2_2") (pintype "passive"))
      (node (ref "c5") (pin "2") (pinfunction "2_2") (pintype "passive"))
    )
    (net (code "8") (name "/+5V{slash}+3V3_328P_AVCC") (class "Default")
      (node (ref "FB3") (pin "2") (pinfunction "2_2") (pintype "passive"))
      (node (ref "U1") (pin "20") (pinfunction "AVCC_20") (pintype "passive"))
      (node (ref "c22") (pin "2") (pinfunction "2_2") (pintype "passive"))
      (node (ref "c23") (pin "2") (pinfunction "2_2") (pintype "passive"))
    )
    (net (code "9") (name "/+5V{slash}+3V3_328P_VCC") (class "Default")
      (node (ref "FB2") (pin "2") (pinfunction "2_2") (pintype "passive"))
      (node (ref "U1") (pin "7") (pinfunction "VCC_7") (pintype "passive"))
      (node (ref "c19") (pin "2") (pinfunction "2_2") (pintype "passive"))
      (node (ref "c20") (pin "2") (pinfunction "2_2") (pintype "passive"))
    )
    (net (code "10") (name "/16U2-RESET") (class "Default")
      (node (ref "JP3") (pin "4") (pinfunction "4_4") (pintype "passive"))
      (node (ref "R4") (pin "1") (pinfunction "1_1") (pintype "passive"))
      (node (ref "U2") (pin "24") (pinfunction "Reset_(PC1_/_dW)_24") (pintype "passive"))
      (node (ref "U5") (pin "4") (pinfunction "4_4") (pintype "passive"))
    )
    (net (code "11") (name "/16U2PROG_328P_RESETn") (class "Default")
      (node (ref "JP1") (pin "2") (pinfunction "2_2") (pintype "passive"))
      (node (ref "R1") (pin "1") (pinfunction "1_1") (pintype "passive"))
      (node (ref "U2") (pin "13") (pinfunction "/_HWB_/_AIN6_/_T0_/_INT7)_PD7_13") (pintype "passive"))
    )
    (net (code "12") (name "/16U2_16MHZ_XTAL1") (class "Default")
      (node (ref "C10") (pin "2") (pinfunction "2_2") (pintype "passive"))
      (node (ref "R9") (pin "1") (pinfunction "1_1") (pintype "passive"))
      (node (ref "U2") (pin "1") (pinfunction "XTAL1_1") (pintype "passive"))
      (node (ref "Y2") (pin "1") (pinfunction "1_1") (pintype "passive"))
    )
    (net (code "13") (name "/16U2_16MHZ_XTAL2") (class "Default")
      (node (ref "C9") (pin "2") (pinfunction "2_2") (pintype "passive"))
      (node (ref "R9") (pin "2") (pinfunction "2_2") (pintype "passive"))
      (node (ref "U2") (pin "2") (pinfunction "(PC0)_XTAL2_2") (pintype "passive"))
      (node (ref "Y2") (pin "2") (pinfunction "2_2") (pintype "passive"))
    )
    (net (code "14") (name "/16U2_BUF_RESETn") (class "Default")
      (node (ref "R23") (pin "2") (pinfunction "2_2") (pintype "passive"))
      (node (ref "U5") (pin "1") (pinfunction "1_1") (pintype "passive"))
      (node (ref "U5") (pin "2") (pinfunction "2_2") (pintype "passive"))
      (node (ref "c31") (pin "2") (pinfunction "2_2") (pintype "passive"))
    )
    (net (code "15") (name "/16U2_HDR_RESETn") (class "Default")
      (node (ref "J6") (pin "5") (pinfunction "5_5") (pintype "passive"))
      (node (ref "JP3") (pin "3") (pinfunction "3_3") (pintype "passive"))
    )
    (net (code "16") (name "/16U2_MISO") (class "Default")
      (node (ref "J6") (pin "1") (pinfunction "1_1") (pintype "passive"))
      (node (ref "U2") (pin "17") (pinfunction "PB3_(PDO_/_MISO_/_PCINT3)_17") (pintype "passive"))
    )
    (net (code "17") (name "/16U2_MOSI") (class "Default")
      (node (ref "J6") (pin "4") (pinfunction "4_4") (pintype "passive"))
      (node (ref "U2") (pin "16") (pinfunction "(PDI_/_MOSI_/_PCINT2)_PB2_16") (pintype "passive"))
    )
    (net (code "18") (name "/16U2_PB4") (class "Default")
      (node (ref "JP2") (pin "1") (pinfunction "1_1") (pintype "passive"))
      (node (ref "JP3") (pin "2") (pinfunction "2_2") (pintype "passive"))
      (node (ref "U2") (pin "18") (pinfunction "PB4_(T1_/_PCINT4)_18") (pintype "passive"))
    )
    (net (code "19") (name "/16U2_PB5") (class "Default")
      (node (ref "JP2") (pin "3") (pinfunction "3_3") (pintype "passive"))
      (node (ref "U2") (pin "19") (pinfunction "PB5_(PCINT5)_19") (pintype "passive"))
    )
    (net (code "20") (name "/16U2_PB6") (class "Default")
      (node (ref "JP2") (pin "2") (pinfunction "2_2") (pintype "passive"))
      (node (ref "U2") (pin "20") (pinfunction "PB6_(PCINT6)_20") (pintype "passive"))
    )
    (net (code "21") (name "/16U2_PB7") (class "Default")
      (node (ref "JP2") (pin "4") (pinfunction "4_4") (pintype "passive"))
      (node (ref "U2") (pin "21") (pinfunction "PB7_(PCINT7_/_OC.0A_/_OC.1C)_21") (pintype "passive"))
    )
    (net (code "22") (name "/16U2_RXD") (class "Default")
      (node (ref "R11") (pin "1") (pinfunction "1_1") (pintype "passive"))
      (node (ref "U2") (pin "8") (pinfunction "(RXD1_/_AIN1_/_INT2)_PD2_8") (pintype "passive"))
    )
    (net (code "23") (name "/16U2_RX_LED") (class "Default")
      (node (ref "D4") (pin "1") (pinfunction "Cathode_1") (pintype "passive"))
      (node (ref "U2") (pin "10") (pinfunction "INT5/_AIN3)_PD4_10") (pintype "passive"))
    )
    (net (code "24") (name "/16U2_SCLK") (class "Default")
      (node (ref "J6") (pin "3") (pinfunction "3_3") (pintype "passive"))
      (node (ref "R5") (pin "2") (pinfunction "2_2") (pintype "passive"))
    )
    (net (code "25") (name "/16U2_SCLK_R") (class "Default")
      (node (ref "R5") (pin "1") (pinfunction "1_1") (pintype "passive"))
      (node (ref "U2") (pin "15") (pinfunction "SCLK_/_PCINT1)_PB1_15") (pintype "passive"))
    )
    (net (code "26") (name "/16U2_TXD") (class "Default")
      (node (ref "R10") (pin "1") (pinfunction "1_1") (pintype "passive"))
      (node (ref "U2") (pin "9") (pinfunction "TXD1_/_INT3)_PD3_9") (pintype "passive"))
    )
    (net (code "27") (name "/16U2_TX_LED") (class "Default")
      (node (ref "D3") (pin "1") (pinfunction "Cathode_1") (pintype "passive"))
      (node (ref "U2") (pin "11") (pinfunction "XCK_AIN4_/_PCINT12)_PD5_11") (pintype "passive"))
    )
    (net (code "28") (name "/328P-Auto_Resetn") (class "Default")
      (node (ref "R18") (pin "1") (pinfunction "1_1") (pintype "passive"))
      (node (ref "U6") (pin "1") (pinfunction "1_1") (pintype "passive"))
      (node (ref "c11") (pin "1") (pinfunction "1_1") (pintype "passive"))
    )
    (net (code "29") (name "/328P-Buf_Resetn") (class "Default")
      (node (ref "R24") (pin "2") (pinfunction "2_2") (pintype "passive"))
      (node (ref "U6") (pin "2") (pinfunction "2_2") (pintype "passive"))
      (node (ref "c32") (pin "2") (pinfunction "2_2") (pintype "passive"))
    )
    (net (code "30") (name "/328P-RESET") (class "Default")
      (node (ref "J1") (pin "3") (pinfunction "3_3") (pintype "passive"))
      (node (ref "J5") (pin "5") (pinfunction "5_5") (pintype "passive"))
      (node (ref "JP3") (pin "1") (pinfunction "1_1") (pintype "passive"))
      (node (ref "R14") (pin "1") (pinfunction "1_1") (pintype "passive"))
      (node (ref "U1") (pin "1") (pinfunction "(PCINT14/~{RESET})_PC6_1") (pintype "passive"))
      (node (ref "U6") (pin "4") (pinfunction "4_4") (pintype "passive"))
    )
    (net (code "31") (name "/328P_16MHZ_XTAL1") (class "Default")
      (node (ref "C27") (pin "2") (pinfunction "2_2") (pintype "passive"))
      (node (ref "R16") (pin "1") (pinfunction "1_1") (pintype "passive"))
      (node (ref "U1") (pin "9") (pinfunction "(PCINT6/XTAL1/TOSC1)_PB6_9") (pintype "passive"))
      (node (ref "Y1") (pin "1") (pinfunction "1_1") (pintype "passive"))
    )
    (net (code "32") (name "/328P_16MHZ_XTAL2") (class "Default")
      (node (ref "C25") (pin "2") (pinfunction "2_2") (pintype "passive"))
      (node (ref "R16") (pin "2") (pinfunction "2_2") (pintype "passive"))
      (node (ref "U1") (pin "10") (pinfunction "(PCINT7/XTAL2/TOSC2)_PB7_10") (pintype "passive"))
      (node (ref "Y1") (pin "2") (pinfunction "2_2") (pintype "passive"))
    )
    (net (code "33") (name "/AD0") (class "Default")
      (node (ref "J2") (pin "1") (pinfunction "1_1") (pintype "passive"))
      (node (ref "U1") (pin "23") (pinfunction "PC0_(ADC0/PCINT8)_23") (pintype "passive"))
    )
    (net (code "34") (name "/AD1") (class "Default")
      (node (ref "J2") (pin "2") (pinfunction "2_2") (pintype "passive"))
      (node (ref "U1") (pin "24") (pinfunction "PC1_(ADC1/PCINT9)_24") (pintype "passive"))
    )
    (net (code "35") (name "/AD2") (class "Default")
      (node (ref "J2") (pin "3") (pinfunction "3_3") (pintype "passive"))
      (node (ref "U1") (pin "25") (pinfunction "PC2_(ADC2/PCINT10)_25") (pintype "passive"))
    )
    (net (code "36") (name "/AD3") (class "Default")
      (node (ref "J2") (pin "4") (pinfunction "4_4") (pintype "passive"))
      (node (ref "U1") (pin "26") (pinfunction "PC3_(ADC3/PCINT11)_26") (pintype "passive"))
    )
    (net (code "37") (name "/AD4{slash}SDA") (class "Default")
      (node (ref "J2") (pin "5") (pinfunction "5_5") (pintype "passive"))
      (node (ref "J4") (pin "9") (pinfunction "9_9") (pintype "passive"))
      (node (ref "U1") (pin "27") (pinfunction "PC4_(ADC4/SDA/PCINT12)_27") (pintype "passive"))
    )
    (net (code "38") (name "/AD5{slash}SCL") (class "Default")
      (node (ref "J2") (pin "6") (pinfunction "6_6") (pintype "passive"))
      (node (ref "J4") (pin "10") (pinfunction "10_10") (pintype "passive"))
      (node (ref "U1") (pin "28") (pinfunction "PC5_(ADC5/SCL/PCINT13)_28") (pintype "passive"))
    )
    (net (code "39") (name "/BUTTON_RESETn") (class "Default")
      (node (ref "D6") (pin "2") (pinfunction "Anode_2") (pintype "passive"))
      (node (ref "R20") (pin "1") (pinfunction "1_1") (pintype "passive"))
      (node (ref "R24") (pin "1") (pinfunction "1_1") (pintype "passive"))
      (node (ref "SW1") (pin "1") (pinfunction "1_1") (pintype "passive"))
      (node (ref "SW1") (pin "2") (pinfunction "2_2") (pintype "passive"))
    )
    (net (code "40") (name "/CON_USB_N") (class "Default")
      (node (ref "J7") (pin "2") (pinfunction "2_2") (pintype "passive"))
      (node (ref "R6") (pin "1") (pinfunction "1_1") (pintype "passive"))
      (node (ref "Z2") (pin "2") (pinfunction "2_2") (pintype "passive"))
    )
    (net (code "41") (name "/CON_USB_P") (class "Default")
      (node (ref "J7") (pin "3") (pinfunction "3_3") (pintype "passive"))
      (node (ref "R7") (pin "1") (pinfunction "1_1") (pintype "passive"))
      (node (ref "Z1") (pin "2") (pinfunction "2_2") (pintype "passive"))
    )
    (net (code "42") (name "/IO0") (class "Default")
      (node (ref "J3") (pin "1") (pinfunction "1_1") (pintype "passive"))
      (node (ref "R10") (pin "2") (pinfunction "2_2") (pintype "passive"))
      (node (ref "U1") (pin "2") (pinfunction "(PCINT16/RXD)_PD0_2") (pintype "passive"))
    )
    (net (code "43") (name "/IO1") (class "Default")
      (node (ref "J3") (pin "2") (pinfunction "2_2") (pintype "passive"))
      (node (ref "R11") (pin "2") (pinfunction "2_2") (pintype "passive"))
      (node (ref "U1") (pin "3") (pinfunction "(PCINT17/TXD)_PD1_3") (pintype "passive"))
    )
    (net (code "44") (name "/IO2") (class "Default")
      (node (ref "J3") (pin "3") (pinfunction "3_3") (pintype "passive"))
      (node (ref "U1") (pin "4") (pinfunction "(PCINT18/INT0)_PD2_4") (pintype "passive"))
    )
    (net (code "45") (name "/IO3") (class "Default")
      (node (ref "J3") (pin "4") (pinfunction "4_4") (pintype "passive"))
      (node (ref "U1") (pin "5") (pinfunction "(PCINT19/OC2B/INT1)_PD3_5") (pintype "passive"))
    )
    (net (code "46") (name "/IO4") (class "Default")
      (node (ref "J3") (pin "5") (pinfunction "5_5") (pintype "passive"))
      (node (ref "U1") (pin "6") (pinfunction "(PCINT20/XCK/T0)_PD4_6") (pintype "passive"))
    )
    (net (code "47") (name "/IO5") (class "Default")
      (node (ref "J3") (pin "6") (pinfunction "6_6") (pintype "passive"))
      (node (ref "U1") (pin "11") (pinfunction "(PCINT21/OC0B/T1)_PD5_11") (pintype "passive"))
    )
    (net (code "48") (name "/IO6") (class "Default")
      (node (ref "J3") (pin "7") (pinfunction "7_7") (pintype "passive"))
      (node (ref "U1") (pin "12") (pinfunction "(PCINT22/OC0A/AIN0)_PD6_12") (pintype "passive"))
    )
    (net (code "49") (name "/IO7") (class "Default")
      (node (ref "J3") (pin "8") (pinfunction "8_8") (pintype "passive"))
      (node (ref "U1") (pin "13") (pinfunction "(PCINT23/AIN1)_PD7_13") (pintype "passive"))
    )
    (net (code "50") (name "/IO8") (class "Default")
      (node (ref "J4") (pin "1") (pinfunction "1_1") (pintype "passive"))
      (node (ref "R22") (pin "2") (pinfunction "2_2") (pintype "passive"))
      (node (ref "U1") (pin "14") (pinfunction "(PCINT0/CLKO/ICP1)_PB0_14") (pintype "passive"))
    )
    (net (code "51") (name "/IO9") (class "Default")
      (node (ref "J4") (pin "2") (pinfunction "2_2") (pintype "passive"))
      (node (ref "U1") (pin "15") (pinfunction "PB1_(OC1A/PCINT1)_15") (pintype "passive"))
    )
    (net (code "52") (name "/MISO") (class "Default")
      (node (ref "J4") (pin "5") (pinfunction "5_5") (pintype "passive"))
      (node (ref "J5") (pin "1") (pinfunction "1_1") (pintype "passive"))
      (node (ref "U1") (pin "18") (pinfunction "PB4_(MISO/PCINT4)_18") (pintype "passive"))
    )
    (net (code "53") (name "/MOSI") (class "Default")
      (node (ref "J4") (pin "4") (pinfunction "4_4") (pintype "passive"))
      (node (ref "J5") (pin "4") (pinfunction "4_4") (pintype "passive"))
      (node (ref "U1") (pin "17") (pinfunction "PB3_(MOSI/OC2A/PCINT3)_17") (pintype "passive"))
    )
    (net (code "54") (name "/SCK") (class "Default")
      (node (ref "J4") (pin "6") (pinfunction "6_6") (pintype "passive"))
      (node (ref "J5") (pin "3") (pinfunction "3_3") (pintype "passive"))
      (node (ref "R13") (pin "2") (pinfunction "2_2") (pintype "passive"))
      (node (ref "U4") (pin "1") (pinfunction "1_1") (pintype "passive"))
      (node (ref "U4") (pin "2") (pinfunction "2_2") (pintype "passive"))
    )
    (net (code "55") (name "/SCK_R") (class "Default")
      (node (ref "R13") (pin "1") (pinfunction "1_1") (pintype "passive"))
      (node (ref "U1") (pin "19") (pinfunction "PB5_(SCK/PCINT5)_19") (pintype "passive"))
    )
    (net (code "56") (name "/SS") (class "Default")
      (node (ref "J4") (pin "3") (pinfunction "3_3") (pintype "passive"))
      (node (ref "U1") (pin "16") (pinfunction "PB2_(SS/OC1B/PCINT2)_16") (pintype "passive"))
    )
    (net (code "57") (name "/USB_N") (class "Default")
      (node (ref "R6") (pin "2") (pinfunction "2_2") (pintype "passive"))
      (node (ref "U2") (pin "30") (pinfunction "D-_30") (pintype "passive"))
    )
    (net (code "58") (name "/USB_P") (class "Default")
      (node (ref "R7") (pin "2") (pinfunction "2_2") (pintype "passive"))
      (node (ref "U2") (pin "29") (pinfunction "D+_29") (pintype "passive"))
    )
    (net (code "59") (name "/USER_BUTTON") (class "Default")
      (node (ref "R21") (pin "1") (pinfunction "1_1") (pintype "passive"))
      (node (ref "R25") (pin "1") (pinfunction "1_1") (pintype "passive"))
      (node (ref "SW2") (pin "1") (pinfunction "1_1") (pintype "passive"))
      (node (ref "SW2") (pin "2") (pinfunction "2_2") (pintype "passive"))
    )
    (net (code "60") (name "/USER_BUTTON_BUF") (class "Default")
      (node (ref "R25") (pin "2") (pinfunction "2_2") (pintype "passive"))
      (node (ref "U7") (pin "1") (pinfunction "1_1") (pintype "passive"))
      (node (ref "U7") (pin "2") (pinfunction "2_2") (pintype "passive"))
      (node (ref "c33") (pin "2") (pinfunction "2_2") (pintype "passive"))
    )
    (net (code "61") (name "GND") (class "Default")
      (node (ref "C1") (pin "2") (pinfunction "2_2") (pintype "passive"))
      (node (ref "C10") (pin "1") (pinfunction "1_1") (pintype "passive"))
      (node (ref "C2") (pin "2") (pinfunction "2_2") (pintype "passive"))
      (node (ref "C25") (pin "1") (pinfunction "1_1") (pintype "passive"))
      (node (ref "C27") (pin "1") (pinfunction "1_1") (pintype "passive"))
      (node (ref "C7") (pin "1") (pinfunction "1_1") (pintype "passive"))
      (node (ref "C9") (pin "1") (pinfunction "1_1") (pintype "passive"))
      (node (ref "D1") (pin "1") (pinfunction "Cathode_1") (pintype "passive"))
      (node (ref "J1") (pin "6") (pinfunction "6_6") (pintype "passive"))
      (node (ref "J1") (pin "7") (pinfunction "7_7") (pintype "passive"))
      (node (ref "J4") (pin "7") (pinfunction "7_7") (pintype "passive"))
      (node (ref "J5") (pin "6") (pinfunction "6_6") (pintype "passive"))
      (node (ref "J6") (pin "6") (pinfunction "6_6") (pintype "passive"))
      (node (ref "J7") (pin "10") (pinfunction "10_10") (pintype "passive"))
      (node (ref "J7") (pin "11") (pinfunction "11_11") (pintype "passive"))
      (node (ref "J7") (pin "5") (pinfunction "5_5") (pintype "passive"))
      (node (ref "J7") (pin "6") (pinfunction "6_6") (pintype "passive"))
      (node (ref "J7") (pin "7") (pinfunction "7_7") (pintype "passive"))
      (node (ref "J7") (pin "8") (pinfunction "8_8") (pintype "passive"))
      (node (ref "J7") (pin "9") (pinfunction "9_9") (pintype "passive"))
      (node (ref "J9") (pin "1") (pinfunction "1_1") (pintype "open_collector"))
      (node (ref "MH1") (pin "1") (pinfunction "1_1") (pintype "passive"))
      (node (ref "MH2") (pin "1") (pinfunction "1_1") (pintype "passive"))
      (node (ref "MH3") (pin "1") (pinfunction "1_1") (pintype "passive"))
      (node (ref "R12") (pin "1") (pinfunction "1_1") (pintype "passive"))
      (node (ref "R8") (pin "1") (pinfunction "1_1") (pintype "passive"))
      (node (ref "SW1") (pin "3") (pinfunction "3_3") (pintype "passive"))
      (node (ref "SW1") (pin "4") (pinfunction "4_4") (pintype "passive"))
      (node (ref "SW2") (pin "3") (pinfunction "3_3") (pintype "passive"))
      (node (ref "SW2") (pin "4") (pinfunction "4_4") (pintype "passive"))
      (node (ref "U1") (pin "22") (pinfunction "GND_22") (pintype "passive"))
      (node (ref "U1") (pin "8") (pinfunction "GND_8") (pintype "passive"))
      (node (ref "U3") (pin "3") (pinfunction "GND_3") (pintype "passive"))
      (node (ref "U3") (pin "6") (pinfunction "EPAD_6") (pintype "passive"))
      (node (ref "U4") (pin "3") (pinfunction "3_3") (pintype "passive"))
      (node (ref "U5") (pin "3") (pinfunction "3_3") (pintype "passive"))
      (node (ref "U6") (pin "3") (pinfunction "3_3") (pintype "passive"))
      (node (ref "U7") (pin "3") (pinfunction "3_3") (pintype "passive"))
      (node (ref "Z1") (pin "1") (pinfunction "1_1") (pintype "passive"))
      (node (ref "Z2") (pin "1") (pinfunction "1_1") (pintype "passive"))
      (node (ref "c12") (pin "2") (pinfunction "2_2") (pintype "passive"))
      (node (ref "c13") (pin "2") (pinfunction "2_2") (pintype "passive"))
      (node (ref "c14") (pin "1") (pinfunction "1_1") (pintype "passive"))
      (node (ref "c15") (pin "1") (pinfunction "1_1") (pintype "passive"))
      (node (ref "c16") (pin "1") (pinfunction "1_1") (pintype "passive"))
      (node (ref "c17") (pin "1") (pinfunction "1_1") (pintype "passive"))
      (node (ref "c19") (pin "1") (pinfunction "1_1") (pintype "passive"))
      (node (ref "c20") (pin "1") (pinfunction "1_1") (pintype "passive"))
      (node (ref "c21") (pin "1") (pinfunction "1_1") (pintype "passive"))
      (node (ref "c22") (pin "1") (pinfunction "1_1") (pintype "passive"))
      (node (ref "c23") (pin "1") (pinfunction "1_1") (pintype "passive"))
      (node (ref "c24") (pin "1") (pinfunction "1_1") (pintype "passive"))
      (node (ref "c26") (pin "1") (pinfunction "1_1") (pintype "passive"))
      (node (ref "c28") (pin "2") (pinfunction "2_2") (pintype "passive"))
      (node (ref "c29") (pin "2") (pinfunction "2_2") (pintype "passive"))
      (node (ref "c3") (pin "1") (pinfunction "1_1") (pintype "passive"))
      (node (ref "c30") (pin "2") (pinfunction "2_2") (pintype "passive"))
      (node (ref "c31") (pin "1") (pinfunction "1_1") (pintype "passive"))
      (node (ref "c32") (pin "1") (pinfunction "1_1") (pintype "passive"))
      (node (ref "c33") (pin "1") (pinfunction "1_1") (pintype "passive"))
      (node (ref "c34") (pin "1") (pinfunction "1_1") (pintype "passive"))
      (node (ref "c4") (pin "1") (pinfunction "1_1") (pintype "passive"))
      (node (ref "c5") (pin "1") (pinfunction "1_1") (pintype "passive"))
      (node (ref "c6") (pin "1") (pinfunction "1_1") (pintype "passive"))
      (node (ref "c8") (pin "1") (pinfunction "1_1") (pintype "passive"))
    )
    (net (code "62") (name "Net-(D1-Anode)") (class "Default")
      (node (ref "D1") (pin "2") (pinfunction "Anode_2") (pintype "passive"))
      (node (ref "R17") (pin "2") (pinfunction "2_2") (pintype "passive"))
    )
    (net (code "63") (name "Net-(D2-Anode)") (class "Default")
      (node (ref "D2") (pin "2") (pinfunction "Anode_2") (pintype "passive"))
      (node (ref "R15") (pin "1") (pinfunction "1_1") (pintype "passive"))
    )
    (net (code "64") (name "Net-(D2-Cathode)") (class "Default")
      (node (ref "D2") (pin "1") (pinfunction "Cathode_1") (pintype "passive"))
      (node (ref "U4") (pin "4") (pinfunction "4_4") (pintype "passive"))
    )
    (net (code "65") (name "Net-(D3-Anode)") (class "Default")
      (node (ref "D3") (pin "2") (pinfunction "Anode_2") (pintype "passive"))
      (node (ref "R2") (pin "1") (pinfunction "1_1") (pintype "passive"))
    )
    (net (code "66") (name "Net-(D4-Anode)") (class "Default")
      (node (ref "D4") (pin "2") (pinfunction "Anode_2") (pintype "passive"))
      (node (ref "R3") (pin "1") (pinfunction "1_1") (pintype "passive"))
    )
    (net (code "67") (name "Net-(D5-Anode)") (class "Default")
      (node (ref "D5") (pin "2") (pinfunction "Anode_2") (pintype "passive"))
      (node (ref "R19") (pin "1") (pinfunction "1_1") (pintype "passive"))
      (node (ref "R23") (pin "1") (pinfunction "1_1") (pintype "passive"))
    )
    (net (code "68") (name "Net-(J7-Pad4)") (class "Default")
      (node (ref "J7") (pin "4") (pinfunction "4_4") (pintype "passive"))
      (node (ref "R8") (pin "2") (pinfunction "2_2") (pintype "passive"))
    )
    (net (code "69") (name "Net-(JP1-Pad1)") (class "Default")
      (node (ref "JP1") (pin "1") (pinfunction "1_1") (pintype "passive"))
      (node (ref "c11") (pin "2") (pinfunction "2_2") (pintype "passive"))
    )
    (net (code "70") (name "Net-(JP1-Pad3)") (class "Default")
      (node (ref "JP1") (pin "3") (pinfunction "3_3") (pintype "passive"))
      (node (ref "R12") (pin "2") (pinfunction "2_2") (pintype "passive"))
    )
    (net (code "71") (name "Net-(R22-Pad1)") (class "Default")
      (node (ref "R22") (pin "1") (pinfunction "1_1") (pintype "passive"))
      (node (ref "U7") (pin "4") (pinfunction "4_4") (pintype "passive"))
    )
    (net (code "72") (name "unconnected-(J1-Pad1)") (class "Default")
      (node (ref "J1") (pin "1") (pinfunction "1_1") (pintype "passive+no_connect"))
    )
    (net (code "73") (name "unconnected-(J1-Pad8)") (class "Default")
      (node (ref "J1") (pin "8") (pinfunction "8_8") (pintype "passive+no_connect"))
    )
    (net (code "74") (name "unconnected-(MH4-Pad1)") (class "Default")
      (node (ref "MH4") (pin "1") (pinfunction "1_1") (pintype "passive+no_connect"))
    )
    (net (code "75") (name "unconnected-(U2-(AIN0_{slash}_INT1)_PD1-Pad7)") (class "Default")
      (node (ref "U2") (pin "7") (pinfunction "(AIN0_/_INT1)_PD1_7") (pintype "passive"))
    )
    (net (code "76") (name "unconnected-(U2-(OC.0B_{slash}_INT0)_PD0-Pad6)") (class "Default")
      (node (ref "U2") (pin "6") (pinfunction "(OC.0B_/_INT0)_PD0_6") (pintype "passive"))
    )
    (net (code "77") (name "unconnected-(U2-(PCINT11_{slash}AIN2_)_PC2-Pad5)") (class "Default")
      (node (ref "U2") (pin "5") (pinfunction "(PCINT11_/AIN2_)_PC2_5") (pintype "passive+no_connect"))
    )
    (net (code "78") (name "unconnected-(U2-GND-Pad3)") (class "Default")
      (node (ref "U2") (pin "3") (pinfunction "GND_3") (pintype "passive"))
    )
    (net (code "79") (name "unconnected-(U2-PC4_(PCINT10)-Pad26)") (class "Default")
      (node (ref "U2") (pin "26") (pinfunction "PC4_(PCINT10)_26") (pintype "passive+no_connect"))
    )
    (net (code "80") (name "unconnected-(U2-PC5_(_PCINT9{slash}_OC.1B)-Pad25)") (class "Default")
      (node (ref "U2") (pin "25") (pinfunction "PC5_(_PCINT9/_OC.1B)_25") (pintype "passive+no_connect"))
    )
    (net (code "81") (name "unconnected-(U2-PC6_(OC.1A_{slash}_PCINT8)-Pad23)") (class "Default")
      (node (ref "U2") (pin "23") (pinfunction "PC6_(OC.1A_/_PCINT8)_23") (pintype "passive+no_connect"))
    )
    (net (code "82") (name "unconnected-(U2-PC7_(INT4_{slash}_ICP1_{slash}_CLKO)-Pad22)") (class "Default")
      (node (ref "U2") (pin "22") (pinfunction "PC7_(INT4_/_ICP1_/_CLKO)_22") (pintype "passive+no_connect"))
    )
    (net (code "83") (name "unconnected-(U2-RTS_{slash}_AIN5_{slash}_INT6)_PD6-Pad12)") (class "Default")
      (node (ref "U2") (pin "12") (pinfunction "RTS_/_AIN5_/_INT6)_PD6_12") (pintype "passive+no_connect"))
    )
    (net (code "84") (name "unconnected-(U2-SS_{slash}_PCINT0)_PB0-Pad14)") (class "Default")
      (node (ref "U2") (pin "14") (pinfunction "SS_/_PCINT0)_PB0_14") (pintype "passive+no_connect"))
    )
    (net (code "85") (name "unconnected-(U2-UGND-Pad28)") (class "Default")
      (node (ref "U2") (pin "28") (pinfunction "UGND_28") (pintype "passive"))
    )
  )
)
